# Amp_2.net
KiCad netlist of a schematic drawn in Altium Designer
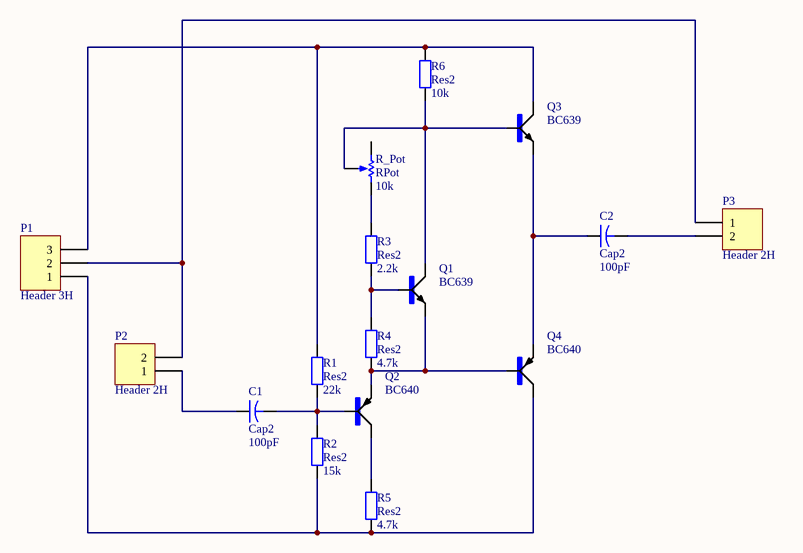
[diagram p0: Amp_2.SchDoc]

(export (version "E")
  (design (tool "Eeschema 10.0.6"))
  (components
    (comp (ref "C1")
      (value "Cap2")
      (footprint "CAPR5-4X5")
      (description "Capacitor")
      (fields (field (name "ALTIUM_VALUE") "100pF") (field (name "PUBLISHER") "Altium Limited"))
      (libsource (lib "Miscellaneous Devices") (part "Cap2"))
    )
    (comp (ref "C2")
      (value "Cap2")
      (footprint "CAPR5-4X5")
      (description "Capacitor")
      (fields (field (name "ALTIUM_VALUE") "100pF") (field (name "PUBLISHER") "Altium Limited"))
      (libsource (lib "Miscellaneous Devices") (part "Cap2"))
    )
    (comp (ref "P1")
      (value "Header 3H")
      (footprint "HDR1X3H")
      (description "Header, 3-Pin, Right Angle")
      (fields (field (name "PUBLISHER") "Altium Limited"))
      (libsource (lib "Miscellaneous Connectors") (part "Header 3H"))
    )
    (comp (ref "P2")
      (value "Header 2H")
      (footprint "HDR1X2H")
      (description "Header, 2-Pin, Right Angle")
      (fields (field (name "PUBLISHER") "Altium Limited"))
      (libsource (lib "") (part "Header 2H_1"))
    )
    (comp (ref "P3")
      (value "Header 2H")
      (footprint "HDR1X2H")
      (description "Header, 2-Pin, Right Angle")
      (fields (field (name "PUBLISHER") "Altium Limited"))
      (libsource (lib "Miscellaneous Connectors") (part "Header 2H"))
    )
    (comp (ref "Q1")
      (value "BC639")
      (footprint "*SOT54D_BC639(Primary)")
      (description "Bipolar _BJT_ Transistor NPN 80V 1A 200MHz 625mW Through Hole TO-92-3")
      (fields (field (name "MF") "ON Semiconductor"))
      (libsource (lib "BC639") (part "BC639"))
    )
    (comp (ref "Q2")
      (value "BC640")
      (footprint "*SOT54D_BC640(Primary)")
      (description "Bipolar _BJT_ Transistor PNP 80V 500mA 150MHz 625mW Through Hole TO-92-3")
      (fields (field (name "MF") "ON Semiconductor"))
      (libsource (lib "BC640") (part "BC640"))
    )
    (comp (ref "Q3")
      (value "BC639")
      (footprint "*SOT54D_BC639(Primary)")
      (description "Bipolar _BJT_ Transistor NPN 80V 1A 200MHz 625mW Through Hole TO-92-3")
      (fields (field (name "MF") "ON Semiconductor"))
      (libsource (lib "BC639") (part "BC639"))
    )
    (comp (ref "Q4")
      (value "BC640")
      (footprint "*SOT54D_BC640(Primary)")
      (description "Bipolar _BJT_ Transistor PNP 80V 500mA 150MHz 625mW Through Hole TO-92-3")
      (fields (field (name "MF") "ON Semiconductor"))
      (libsource (lib "BC640") (part "BC640"))
    )
    (comp (ref "R1")
      (value "Res2")
      (footprint "AXIAL-0.4")
      (description "Resistor")
      (fields (field (name "ALTIUM_VALUE") "22k") (field (name "PUBLISHER") "Altium Limited"))
      (libsource (lib "Miscellaneous Devices") (part "Res2"))
    )
    (comp (ref "R2")
      (value "Res2")
      (footprint "AXIAL-0.4")
      (description "Resistor")
      (fields (field (name "ALTIUM_VALUE") "15k") (field (name "PUBLISHER") "Altium Limited"))
      (libsource (lib "Miscellaneous Devices") (part "Res2"))
    )
    (comp (ref "R3")
      (value "Res2")
      (footprint "AXIAL-0.4")
      (description "Resistor")
      (fields (field (name "ALTIUM_VALUE") "2.2k") (field (name "PUBLISHER") "Altium Limited"))
      (libsource (lib "Miscellaneous Devices") (part "Res2"))
    )
    (comp (ref "R4")
      (value "Res2")
      (footprint "AXIAL-0.4")
      (description "Resistor")
      (fields (field (name "ALTIUM_VALUE") "4.7k") (field (name "PUBLISHER") "Altium Limited"))
      (libsource (lib "Miscellaneous Devices") (part "Res2"))
    )
    (comp (ref "R5")
      (value "Res2")
      (footprint "AXIAL-0.4")
      (description "Resistor")
      (fields (field (name "ALTIUM_VALUE") "4.7k") (field (name "PUBLISHER") "Altium Limited"))
      (libsource (lib "Miscellaneous Devices") (part "Res2"))
    )
    (comp (ref "R6")
      (value "Res2")
      (footprint "AXIAL-0.4")
      (description "Resistor")
      (fields (field (name "ALTIUM_VALUE") "10k") (field (name "PUBLISHER") "Altium Limited"))
      (libsource (lib "Miscellaneous Devices") (part "Res2"))
    )
    (comp (ref "R_Pot")
      (value "RPot")
      (footprint "VR5")
      (description "Potentiometer")
      (fields (field (name "ALTIUM_VALUE") "10k") (field (name "PUBLISHER") "Altium Limited"))
      (libsource (lib "Miscellaneous Devices") (part "RPot"))
    )
  )
  (nets
    (net (code "1") (name "Net-(C1-Pad1)") (class "Default")
      (node (ref "C1") (pin "1") (pinfunction "1_1") (pintype "passive"))
      (node (ref "P2") (pin "1") (pinfunction "1_1") (pintype "passive"))
    )
    (net (code "2") (name "Net-(C1-Pad2)") (class "Default")
      (node (ref "C1") (pin "2") (pinfunction "2_2") (pintype "passive"))
      (node (ref "Q2") (pin "B") (pinfunction "B_B") (pintype "passive"))
      (node (ref "R1") (pin "1") (pinfunction "1_1") (pintype "passive"))
      (node (ref "R2") (pin "2") (pinfunction "2_2") (pintype "passive"))
    )
    (net (code "3") (name "Net-(C2-Pad1)") (class "Default")
      (node (ref "C2") (pin "1") (pinfunction "1_1") (pintype "passive"))
      (node (ref "Q3") (pin "E") (pinfunction "E_E") (pintype "passive"))
      (node (ref "Q4") (pin "E") (pinfunction "E_E") (pintype "passive"))
    )
    (net (code "4") (name "Net-(C2-Pad2)") (class "Default")
      (node (ref "C2") (pin "2") (pinfunction "2_2") (pintype "passive"))
      (node (ref "P3") (pin "2") (pinfunction "2_2") (pintype "passive"))
    )
    (net (code "5") (name "Net-(P1-Pad1)") (class "Default")
      (node (ref "P1") (pin "1") (pinfunction "1_1") (pintype "passive"))
      (node (ref "Q4") (pin "C") (pinfunction "C_C") (pintype "passive"))
      (node (ref "R2") (pin "1") (pinfunction "1_1") (pintype "passive"))
      (node (ref "R5") (pin "1") (pinfunction "1_1") (pintype "passive"))
    )
    (net (code "6") (name "Net-(P1-Pad2)") (class "Default")
      (node (ref "P1") (pin "2") (pinfunction "2_2") (pintype "passive"))
      (node (ref "P2") (pin "2") (pinfunction "2_2") (pintype "passive"))
      (node (ref "P3") (pin "1") (pinfunction "1_1") (pintype "passive"))
    )
    (net (code "7") (name "Net-(P1-Pad3)") (class "Default")
      (node (ref "P1") (pin "3") (pinfunction "3_3") (pintype "passive"))
      (node (ref "Q3") (pin "C") (pinfunction "C_C") (pintype "passive"))
      (node (ref "R1") (pin "2") (pinfunction "2_2") (pintype "passive"))
      (node (ref "R6") (pin "2") (pinfunction "2_2") (pintype "passive"))
    )
    (net (code "8") (name "Net-(Q1-PadB)") (class "Default")
      (node (ref "Q1") (pin "B") (pinfunction "B_B") (pintype "passive"))
      (node (ref "R3") (pin "1") (pinfunction "1_1") (pintype "passive"))
      (node (ref "R4") (pin "2") (pinfunction "2_2") (pintype "passive"))
    )
    (net (code "9") (name "Net-(Q1-PadE)") (class "Default")
      (node (ref "Q1") (pin "E") (pinfunction "E_E") (pintype "passive"))
      (node (ref "Q2") (pin "E") (pinfunction "E_E") (pintype "passive"))
      (node (ref "Q4") (pin "B") (pinfunction "B_B") (pintype "passive"))
      (node (ref "R4") (pin "1") (pinfunction "1_1") (pintype "passive"))
    )
    (net (code "10") (name "Net-(Q2-PadC)") (class "Default")
      (node (ref "Q2") (pin "C") (pinfunction "C_C") (pintype "passive"))
      (node (ref "R5") (pin "2") (pinfunction "2_2") (pintype "passive"))
    )
    (net (code "11") (name "Net-(R_Pot-BOT)") (class "Default")
      (node (ref "R3") (pin "2") (pinfunction "2_2") (pintype "passive"))
      (node (ref "R_Pot") (pin "2") (pinfunction "BOT_2") (pintype "passive"))
    )
    (net (code "12") (name "Net-(R_Pot-TAP)") (class "Default")
      (node (ref "Q1") (pin "C") (pinfunction "C_C") (pintype "passive"))
      (node (ref "Q3") (pin "B") (pinfunction "B_B") (pintype "passive"))
      (node (ref "R6") (pin "1") (pinfunction "1_1") (pintype "passive"))
      (node (ref "R_Pot") (pin "3") (pinfunction "TAP_3") (pintype "passive"))
    )
    (net (code "13") (name "unconnected-(R_Pot-TOP-Pad1)") (class "Default")
      (node (ref "R_Pot") (pin "1") (pinfunction "TOP_1") (pintype "passive"))
    )
  )
)
